# GOTEK_Speaker_Curcuit.net
KiCad netlist of a schematic drawn in EAGLE
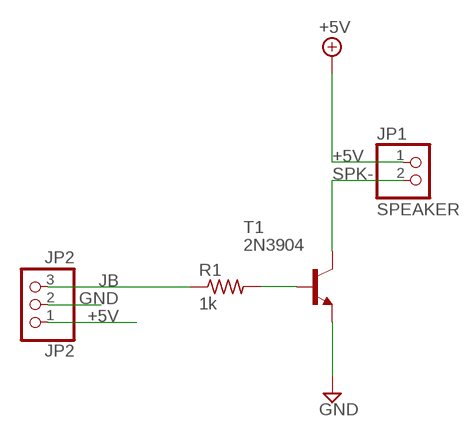
[diagram p0: schematic, sheet 1]

(export (version "E")
  (design (tool "Eeschema 10.0.6"))
  (components
    (comp (ref "JP1")
      (value "SPEAKER")
      (footprint "eagle-import:1X02")
      (libsource (lib "eagle-import") (part "PINHD-1X2"))
    )
    (comp (ref "JP2")
      (value "JP2")
      (footprint "eagle-import:1X03")
      (libsource (lib "eagle-import") (part "PINHD-1X3"))
    )
    (comp (ref "R1")
      (value "1k")
      (footprint "eagle-import:0204_7")
      (libsource (lib "eagle-import") (part "R-US_0204/7"))
    )
    (comp (ref "T1")
      (value "2N3904")
      (footprint "eagle-import:TO92")
      (libsource (lib "eagle-import") (part "2N3904"))
    )
  )
  (nets
    (net (code "1") (name "+5V") (class "Default")
      (node (ref "JP1") (pin "1") (pinfunction "1_1") (pintype "passive"))
      (node (ref "JP2") (pin "1") (pinfunction "1_1") (pintype "passive"))
    )
    (net (code "2") (name "/JB") (class "Default")
      (node (ref "JP2") (pin "3") (pinfunction "3_3") (pintype "passive"))
      (node (ref "R1") (pin "1") (pinfunction "1_1") (pintype "passive"))
    )
    (net (code "3") (name "/SPK-") (class "Default")
      (node (ref "JP1") (pin "2") (pinfunction "2_2") (pintype "passive"))
      (node (ref "T1") (pin "1") (pinfunction "C_1") (pintype "passive"))
    )
    (net (code "4") (name "GND") (class "Default")
      (node (ref "JP2") (pin "2") (pinfunction "2_2") (pintype "passive"))
      (node (ref "T1") (pin "3") (pinfunction "E_3") (pintype "passive"))
    )
    (net (code "5") (name "Net-(T1-B)") (class "Default")
      (node (ref "R1") (pin "2") (pinfunction "2_2") (pintype "passive"))
      (node (ref "T1") (pin "2") (pinfunction "B_2") (pintype "passive"))
    )
  )
)
